# teplomer.net
KiCad netlist of a schematic drawn in EAGLE
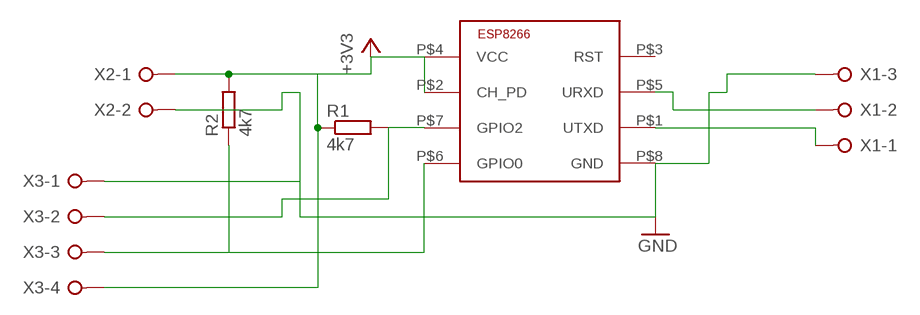
[diagram p0: schematic, sheet 1]

(export (version "E")
  (design (tool "Eeschema 10.0.6"))
  (components
    (comp (ref "R1")
      (value "4k7")
      (footprint "eagle-import:0204_5")
      (libsource (lib "eagle-import") (part "R-EU_0204/5"))
    )
    (comp (ref "R2")
      (value "4k7")
      (footprint "eagle-import:0204_5")
      (libsource (lib "eagle-import") (part "R-EU_0204/5"))
    )
    (comp (ref "U$1")
      (value "ESP8266-01")
      (footprint "eagle-import:ESP-01")
      (libsource (lib "eagle-import") (part "ESP8266-01"))
    )
    (comp (ref "X1")
      (value "W237-3E")
      (footprint "eagle-import:W237-3E")
      (libsource (lib "eagle-import") (part "W237-3E"))
    )
    (comp (ref "X2")
      (value "W237-02P")
      (footprint "eagle-import:W237-132")
      (libsource (lib "eagle-import") (part "W237-02P"))
    )
    (comp (ref "X3")
      (value "W237-04P")
      (footprint "eagle-import:W237-4P")
      (libsource (lib "eagle-import") (part "W237-04P"))
    )
  )
  (nets
    (net (code "1") (name "+3V3") (class "Default")
      (node (ref "R1") (pin "1") (pinfunction "1_1") (pintype "passive"))
      (node (ref "R2") (pin "2") (pinfunction "2_2") (pintype "passive"))
      (node (ref "U$1") (pin "P$2") (pinfunction "CH_PD_P$2") (pintype "bidirectional"))
      (node (ref "U$1") (pin "P$4") (pinfunction "VCC_P$4") (pintype "bidirectional"))
      (node (ref "X2") (pin "1") (pinfunction "KL_1") (pintype "passive"))
      (node (ref "X3") (pin "4") (pinfunction "KL_4") (pintype "passive"))
    )
    (net (code "2") (name "GND") (class "Default")
      (node (ref "U$1") (pin "P$8") (pinfunction "GND_P$8") (pintype "bidirectional"))
      (node (ref "X1") (pin "3") (pinfunction "KL_3") (pintype "passive"))
      (node (ref "X2") (pin "2") (pinfunction "KL_2") (pintype "passive"))
      (node (ref "X3") (pin "1") (pinfunction "KL_1") (pintype "passive"))
    )
    (net (code "3") (name "Net-(U$1-GPIO0)") (class "Default")
      (node (ref "R2") (pin "1") (pinfunction "1_1") (pintype "passive"))
      (node (ref "U$1") (pin "P$6") (pinfunction "GPIO0_P$6") (pintype "bidirectional"))
      (node (ref "X3") (pin "3") (pinfunction "KL_3") (pintype "passive"))
    )
    (net (code "4") (name "Net-(U$1-GPIO2)") (class "Default")
      (node (ref "R1") (pin "2") (pinfunction "2_2") (pintype "passive"))
      (node (ref "U$1") (pin "P$7") (pinfunction "GPIO2_P$7") (pintype "bidirectional"))
      (node (ref "X3") (pin "2") (pinfunction "KL_2") (pintype "passive"))
    )
    (net (code "5") (name "Net-(U$1-URXD)") (class "Default")
      (node (ref "U$1") (pin "P$5") (pinfunction "URXD_P$5") (pintype "bidirectional"))
      (node (ref "X1") (pin "2") (pinfunction "KL_2") (pintype "passive"))
    )
    (net (code "6") (name "Net-(U$1-UTXD)") (class "Default")
      (node (ref "U$1") (pin "P$1") (pinfunction "UTXD_P$1") (pintype "bidirectional"))
      (node (ref "X1") (pin "1") (pinfunction "KL_1") (pintype "passive"))
    )
    (net (code "7") (name "unconnected-(U$1-RST-PadP$3)") (class "Default")
      (node (ref "U$1") (pin "P$3") (pinfunction "RST_P$3") (pintype "bidirectional"))
    )
  )
)
